# ziegler_sct.net
KiCad netlist of a schematic drawn in EAGLE
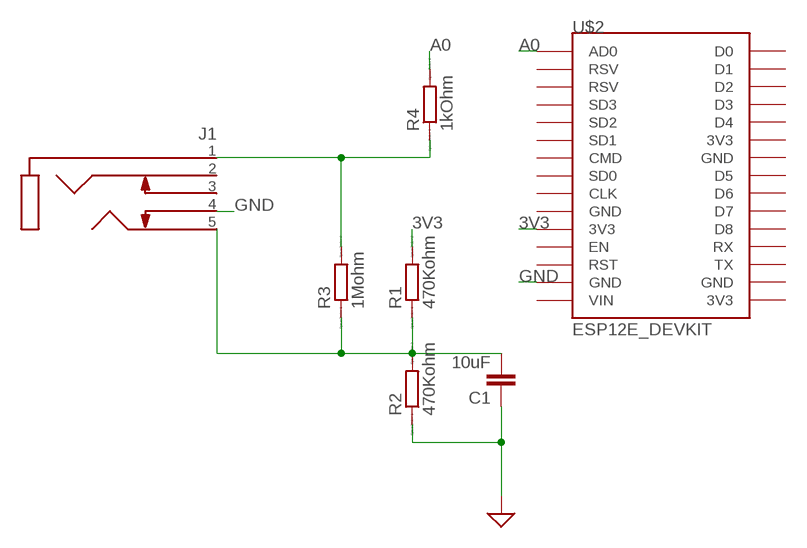
[diagram p0: schematic, sheet 1]

(export (version "E")
  (design (tool "Eeschema 10.0.6"))
  (components
    (comp (ref "C1")
      (value "10uF")
      (footprint "eagle-import:C5B3")
      (libsource (lib "eagle-import") (part "C5/3"))
    )
    (comp (ref "J1")
      (value "STEREO_JACK3F07")
      (footprint "eagle-import:3.5AUDIO_3F07")
      (libsource (lib "eagle-import") (part "STEREO_JACK3F07"))
    )
    (comp (ref "R1")
      (value "470Kohm")
      (footprint "eagle-import:0204_7")
      (libsource (lib "eagle-import") (part "R0204/7"))
    )
    (comp (ref "R2")
      (value "470Kohm")
      (footprint "eagle-import:0204_7")
      (libsource (lib "eagle-import") (part "R0204/7"))
    )
    (comp (ref "R3")
      (value "1Mohm")
      (footprint "eagle-import:0204_7")
      (libsource (lib "eagle-import") (part "R0204/7"))
    )
    (comp (ref "R4")
      (value "1kOhm")
      (footprint "eagle-import:0204_7")
      (libsource (lib "eagle-import") (part "R0204/7"))
    )
    (comp (ref "U$2")
      (value "ESP12E_DEVKIT")
      (footprint "eagle-import:ESP12E_DEVKIT")
      (libsource (lib "eagle-import") (part "ESP12E_DEVKIT"))
    )
  )
  (nets
    (net (code "1") (name "/3V3") (class "Default")
      (node (ref "R1") (pin "2") (pinfunction "2_2") (pintype "passive"))
      (node (ref "U$2") (pin "3V3@0") (pinfunction "3V3_3V3@0") (pintype "bidirectional"))
    )
    (net (code "2") (name "/A0") (class "Default")
      (node (ref "R4") (pin "2") (pinfunction "2_2") (pintype "passive"))
      (node (ref "U$2") (pin "AD0") (pinfunction "AD0_AD0") (pintype "bidirectional"))
    )
    (net (code "3") (name "Net-(J1-RING)") (class "Default")
      (node (ref "C1") (pin "2") (pinfunction "2_2") (pintype "passive"))
      (node (ref "J1") (pin "5") (pinfunction "RING_5") (pintype "bidirectional"))
      (node (ref "R1") (pin "1") (pinfunction "1_1") (pintype "passive"))
      (node (ref "R2") (pin "2") (pinfunction "2_2") (pintype "passive"))
      (node (ref "R3") (pin "1") (pinfunction "1_1") (pintype "passive"))
    )
    (net (code "4") (name "Net-(J1-SLEEVE)") (class "Default")
      (node (ref "J1") (pin "1") (pinfunction "SLEEVE_1") (pintype "bidirectional"))
      (node (ref "R3") (pin "2") (pinfunction "2_2") (pintype "passive"))
      (node (ref "R4") (pin "1") (pinfunction "1_1") (pintype "passive"))
    )
    (net (code "5") (name "SUP") (class "Default")
      (node (ref "C1") (pin "1") (pinfunction "1_1") (pintype "passive"))
      (node (ref "J1") (pin "4") (pinfunction "RSWITCH_4") (pintype "bidirectional"))
      (node (ref "R2") (pin "1") (pinfunction "1_1") (pintype "passive"))
      (node (ref "U$2") (pin "GND@1") (pinfunction "GND_GND@1") (pintype "bidirectional"))
    )
    (net (code "6") (name "unconnected-(J1-TIP-Pad2)") (class "Default")
      (node (ref "J1") (pin "2") (pinfunction "TIP_2") (pintype "bidirectional"))
    )
    (net (code "7") (name "unconnected-(J1-TSWITCH-Pad3)") (class "Default")
      (node (ref "J1") (pin "3") (pinfunction "TSWITCH_3") (pintype "bidirectional"))
    )
    (net (code "8") (name "unconnected-(U$2-3V3-Pad3V3@1)") (class "Default")
      (node (ref "U$2") (pin "3V3@1") (pinfunction "3V3_3V3@1") (pintype "bidirectional"))
    )
    (net (code "9") (name "unconnected-(U$2-3V3-Pad3V3@2)") (class "Default")
      (node (ref "U$2") (pin "3V3@2") (pinfunction "3V3_3V3@2") (pintype "bidirectional"))
    )
    (net (code "10") (name "unconnected-(U$2-GND-PadGND@0)") (class "Default")
      (node (ref "U$2") (pin "GND@0") (pinfunction "GND_GND@0") (pintype "bidirectional"))
    )
    (net (code "11") (name "unconnected-(U$2-GND-PadGND@2)") (class "Default")
      (node (ref "U$2") (pin "GND@2") (pinfunction "GND_GND@2") (pintype "bidirectional"))
    )
    (net (code "12") (name "unconnected-(U$2-GND-PadGND@3)") (class "Default")
      (node (ref "U$2") (pin "GND@3") (pinfunction "GND_GND@3") (pintype "bidirectional"))
    )
    (net (code "13") (name "unconnected-(U$2-PadCLK)") (class "Default")
      (node (ref "U$2") (pin "CLK") (pinfunction "CLK_CLK") (pintype "bidirectional"))
    )
    (net (code "14") (name "unconnected-(U$2-PadCMD)") (class "Default")
      (node (ref "U$2") (pin "CMD") (pinfunction "CMD_CMD") (pintype "bidirectional"))
    )
    (net (code "15") (name "unconnected-(U$2-PadD0)") (class "Default")
      (node (ref "U$2") (pin "D0") (pinfunction "D0_D0") (pintype "bidirectional"))
    )
    (net (code "16") (name "unconnected-(U$2-PadD1)") (class "Default")
      (node (ref "U$2") (pin "D1") (pinfunction "D1_D1") (pintype "bidirectional"))
    )
    (net (code "17") (name "unconnected-(U$2-PadD2)") (class "Default")
      (node (ref "U$2") (pin "D2") (pinfunction "D2_D2") (pintype "bidirectional"))
    )
    (net (code "18") (name "unconnected-(U$2-PadD3)") (class "Default")
      (node (ref "U$2") (pin "D3") (pinfunction "D3_D3") (pintype "bidirectional"))
    )
    (net (code "19") (name "unconnected-(U$2-PadD4)") (class "Default")
      (node (ref "U$2") (pin "D4") (pinfunction "D4_D4") (pintype "bidirectional"))
    )
    (net (code "20") (name "unconnected-(U$2-PadD5)") (class "Default")
      (node (ref "U$2") (pin "D5") (pinfunction "D5_D5") (pintype "bidirectional"))
    )
    (net (code "21") (name "unconnected-(U$2-PadD6)") (class "Default")
      (node (ref "U$2") (pin "D6") (pinfunction "D6_D6") (pintype "bidirectional"))
    )
    (net (code "22") (name "unconnected-(U$2-PadD7)") (class "Default")
      (node (ref "U$2") (pin "D7") (pinfunction "D7_D7") (pintype "bidirectional"))
    )
    (net (code "23") (name "unconnected-(U$2-PadD8)") (class "Default")
      (node (ref "U$2") (pin "D8") (pinfunction "D8_D8") (pintype "bidirectional"))
    )
    (net (code "24") (name "unconnected-(U$2-PadEN)") (class "Default")
      (node (ref "U$2") (pin "EN") (pinfunction "EN_EN") (pintype "bidirectional"))
    )
    (net (code "25") (name "unconnected-(U$2-PadRST)") (class "Default")
      (node (ref "U$2") (pin "RST") (pinfunction "RST_RST") (pintype "bidirectional"))
    )
    (net (code "26") (name "unconnected-(U$2-PadRX)") (class "Default")
      (node (ref "U$2") (pin "RX") (pinfunction "RX_RX") (pintype "bidirectional"))
    )
    (net (code "27") (name "unconnected-(U$2-PadSD0)") (class "Default")
      (node (ref "U$2") (pin "SD0") (pinfunction "SD0_SD0") (pintype "bidirectional"))
    )
    (net (code "28") (name "unconnected-(U$2-PadSD1)") (class "Default")
      (node (ref "U$2") (pin "SD1") (pinfunction "SD1_SD1") (pintype "bidirectional"))
    )
    (net (code "29") (name "unconnected-(U$2-PadSD2)") (class "Default")
      (node (ref "U$2") (pin "SD2") (pinfunction "SD2_SD2") (pintype "bidirectional"))
    )
    (net (code "30") (name "unconnected-(U$2-PadSD3)") (class "Default")
      (node (ref "U$2") (pin "SD3") (pinfunction "SD3_SD3") (pintype "bidirectional"))
    )
    (net (code "31") (name "unconnected-(U$2-PadTX)") (class "Default")
      (node (ref "U$2") (pin "TX") (pinfunction "TX_TX") (pintype "bidirectional"))
    )
    (net (code "32") (name "unconnected-(U$2-PadVIN)") (class "Default")
      (node (ref "U$2") (pin "VIN") (pinfunction "VIN_VIN") (pintype "bidirectional"))
    )
    (net (code "33") (name "unconnected-(U$2-RSV-PadRSV@0)") (class "Default")
      (node (ref "U$2") (pin "RSV@0") (pinfunction "RSV_RSV@0") (pintype "bidirectional"))
    )
    (net (code "34") (name "unconnected-(U$2-RSV-PadRSV@1)") (class "Default")
      (node (ref "U$2") (pin "RSV@1") (pinfunction "RSV_RSV@1") (pintype "bidirectional"))
    )
  )
)
